# ADF_2nd_LO_board.net
KiCad netlist of a schematic drawn in Altium Designer
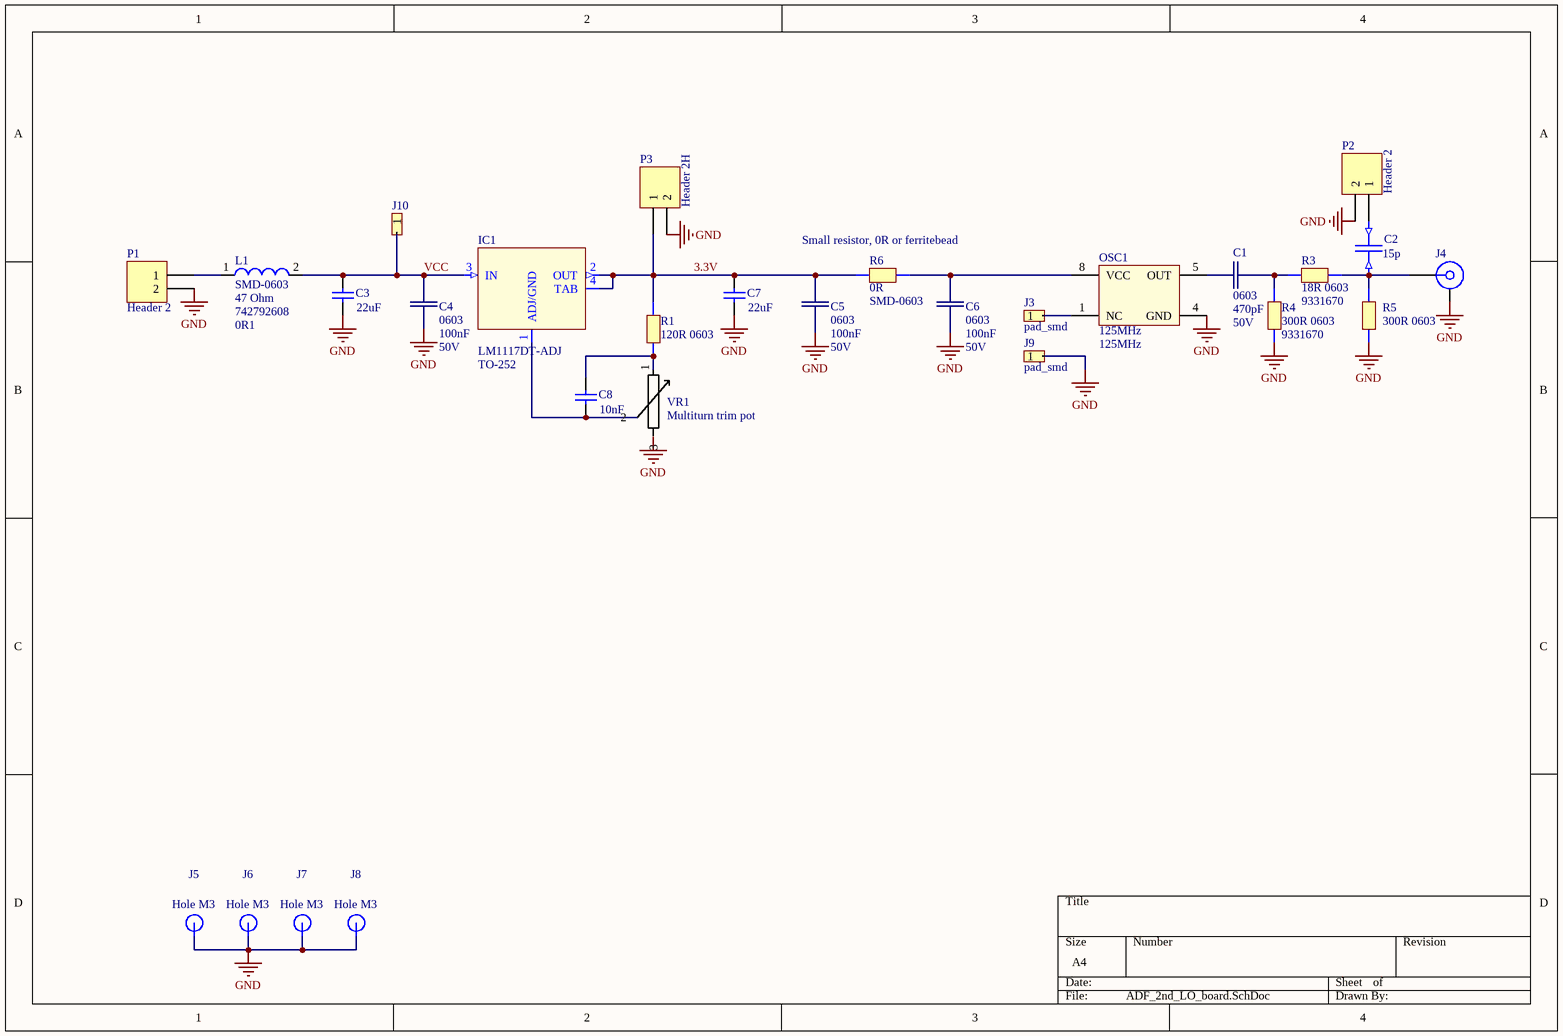
[diagram p0: ADF_2nd_LO_board.SchDoc]

(export (version "E")
  (design (tool "Eeschema 10.0.6"))
  (components
    (comp (ref "C1")
      (value "10nF 0603 NP0")
      (footprint "C0603_murata")
      (description "10nF 0603 NP0 muRata")
      (fields
        (field (name "TOLERANCE") "5%")
        (field (name "CASE CODE (IMPERIAL)") "0603")
        (field (name "CAPACITANCE") "470pF")
        (field (name "VOLTAGE") "50V")
      )
      (libsource (lib "ftg_lib") (part "10nF 0603 NP0"))
    )
    (comp (ref "C2")
      (value "15p")
      (footprint "CAPC1005X04N_0402")
      (description "Class 1 SMD Capacitor")
      (fields
        (field (name "MANUFACTURER") "AVX")
        (field (name "TOLERANCE") "± 5%")
        (field (name "PUBLISHER") "atr")
      )
      (libsource (lib "AQA_atr_2013") (part "Capacitor_15p_0402_C0G"))
    )
    (comp (ref "C3")
      (value "22uF")
      (footprint "C1206")
      (description "Capacitor (Semiconductor SIM Model)")
      (fields (field (name "Comment") "Cap Semi") (field (name "PUBLISHER") "Altium Limited"))
      (libsource (lib "Miscellaneous Devices") (part "Cap Semi"))
    )
    (comp (ref "C4")
      (value "10nF 0603 NP0")
      (footprint "C0603_murata")
      (description "10nF 0603 NP0 muRata")
      (fields
        (field (name "TOLERANCE") "5%")
        (field (name "CASE CODE (IMPERIAL)") "0603")
        (field (name "CAPACITANCE") "100nF")
        (field (name "VOLTAGE") "50V")
      )
      (libsource (lib "ftg_lib") (part "10nF 0603 NP0"))
    )
    (comp (ref "C5")
      (value "10nF 0603 NP0")
      (footprint "C0603_murata")
      (description "10nF 0603 NP0 muRata")
      (fields
        (field (name "TOLERANCE") "5%")
        (field (name "CASE CODE (IMPERIAL)") "0603")
        (field (name "CAPACITANCE") "100nF")
        (field (name "VOLTAGE") "50V")
      )
      (libsource (lib "ftg_lib") (part "10nF 0603 NP0"))
    )
    (comp (ref "C6")
      (value "10nF 0603 NP0")
      (footprint "C0603_murata")
      (description "10nF 0603 NP0 muRata")
      (fields
        (field (name "TOLERANCE") "5%")
        (field (name "CASE CODE (IMPERIAL)") "0603")
        (field (name "CAPACITANCE") "100nF")
        (field (name "VOLTAGE") "50V")
      )
      (libsource (lib "ftg_lib") (part "10nF 0603 NP0"))
    )
    (comp (ref "C7")
      (value "22uF")
      (footprint "C1206")
      (description "Capacitor (Semiconductor SIM Model)")
      (fields (field (name "Comment") "Cap Semi") (field (name "PUBLISHER") "Altium Limited"))
      (libsource (lib "Miscellaneous Devices") (part "Cap Semi"))
    )
    (comp (ref "C8")
      (value "10nF")
      (footprint "1608[0603]")
      (description "Capacitor (Semiconductor SIM Model)")
      (fields (field (name "Comment") "Cap Semi") (field (name "PUBLISHER") "Altium Limited"))
      (libsource (lib "Miscellaneous Devices") (part "Cap Semi"))
    )
    (comp (ref "IC1")
      (value "LM1117DT-ADJ")
      (footprint "TO-252")
      (description "TEXAS INSTRUMENTS  LM1117DT-ADJ  V REG ADJ +1.25/13.8V, 1117, DPAK-3")
      (fields
        (field (name "MANUFACTURER") "TEXAS INSTRUMENTS")
        (field (name "VOLTAGE") "1.25V - 13.8V")
        (field (name "PACKAGEREFERENCE") "TO-252")
        (field (name "PUBLISHER") "atr")
      )
      (libsource (lib "AQA_atr_2013") (part "LM1117DT-ADJ"))
    )
    (comp (ref "J3")
      (value "pad_smd")
      (footprint "pad_smd_bodge")
      (description "1mm * 2mm smd pad")
      (libsource (lib "AQA_Ismolib") (part "pad_smd_1mm*2mm"))
    )
    (comp (ref "J4")
      (value "32K201-400L5")
      (footprint "ROS-32K201-400L5_V")
      (description "SMA Right Angle Jack, Up to 18 GHz, -65 to 165 degC")
      (libsource (lib "Rosenberger SMA") (part "32K201-400L5"))
    )
    (comp (ref "J5")
      (value "Hole M3")
      (footprint "HOLE_M3")
      (description "HoleM3")
      (fields (field (name "TOLERANCE") "N.A.") (field (name "PUBLISHER") "atr"))
      (libsource (lib "AQA_atr_2013") (part "HoleM3"))
    )
    (comp (ref "J6")
      (value "Hole M3")
      (footprint "HOLE_M3")
      (description "HoleM3")
      (fields (field (name "TOLERANCE") "N.A.") (field (name "PUBLISHER") "atr"))
      (libsource (lib "AQA_atr_2013") (part "HoleM3"))
    )
    (comp (ref "J7")
      (value "Hole M3")
      (footprint "HOLE_M3")
      (description "HoleM3")
      (fields (field (name "TOLERANCE") "N.A.") (field (name "PUBLISHER") "atr"))
      (libsource (lib "AQA_atr_2013") (part "HoleM3"))
    )
    (comp (ref "J8")
      (value "Hole M3")
      (footprint "HOLE_M3")
      (description "HoleM3")
      (fields (field (name "TOLERANCE") "N.A.") (field (name "PUBLISHER") "atr"))
      (libsource (lib "AQA_atr_2013") (part "HoleM3"))
    )
    (comp (ref "J9")
      (value "pad_smd")
      (footprint "pad_smd_bodge")
      (description "1mm * 2mm smd pad")
      (libsource (lib "AQA_Ismolib") (part "pad_smd_1mm*2mm"))
    )
    (comp (ref "J10")
      (value "pad_smd")
      (footprint "pad_smd_bodge")
      (description "1mm * 2mm smd pad")
      (libsource (lib "") (part "pad_smd_1mm*2mm_1"))
    )
    (comp (ref "L1")
      (value "742792608")
      (footprint "SMD-0603")
      (description "SMD EMI Suppression Ferrite Bead WE-CBF, Z = 47 Ohm")
      (fields
        (field (name "PACKAGEREFERENCE") "SMD-0603")
        (field (name "IMPEDANCE") "47 Ohm")
        (field (name "DC_RESISTANCE") "0R1")
      )
      (libsource (lib "AQA_20007_4_Flange") (part "742792608"))
    )
    (comp (ref "OSC1")
      (value "125MHz")
      (footprint "DIP-8_osc")
      (description "DIP Oscillator")
      (fields (field (name "FREQUENCY") "125MHz") (field (name "PUBLISHER") "ftg"))
      (libsource (lib "ftg_lib") (part "OSC DIP-8 125MHz 3.3V TTL"))
    )
    (comp (ref "P1")
      (value "Header 2")
      (footprint "HDR1X2")
      (description "Header, 2-Pin")
      (fields (field (name "PUBLISHER") "Altium Limited"))
      (libsource (lib "Miscellaneous Connectors") (part "Header 2"))
    )
    (comp (ref "P2")
      (value "Header 2")
      (footprint "HDR1X2")
      (description "Header, 2-Pin")
      (fields (field (name "PUBLISHER") "Altium Limited"))
      (libsource (lib "") (part "Header 2_1"))
    )
    (comp (ref "P3")
      (value "Header 2H")
      (footprint "HDR1X2H")
      (description "Header, 2-Pin, Right Angle")
      (fields (field (name "PUBLISHER") "Altium Limited"))
      (libsource (lib "Miscellaneous Connectors") (part "Header 2H"))
    )
    (comp (ref "R1")
      (value "120R 0603")
      (footprint "R0603")
      (fields (field (name "MANUFACTURER") "YAGEO (PHYCOMP)") (field (name "PUBLISHER") "iv"))
      (libsource (lib "AQA_Ismolib") (part "0603 120R"))
    )
    (comp (ref "R3")
      (value "18R 0603")
      (footprint "R0603")
      (description "10R 0603")
      (fields
        (field (name "MANUFACTURER") "MULTICOMP")
        (field (name "ORDERCODE") "9331670")
        (field (name "PUBLISHER") "iv")
      )
      (libsource (lib "AQA_Ismolib") (part "0603 10R"))
    )
    (comp (ref "R4")
      (value "300R 0603")
      (footprint "R0603")
      (description "10R 0603")
      (fields
        (field (name "MANUFACTURER") "MULTICOMP")
        (field (name "ORDERCODE") "9331670")
        (field (name "PUBLISHER") "iv")
      )
      (libsource (lib "") (part "0603 10R_2"))
    )
    (comp (ref "R5")
      (value "300R 0603")
      (footprint "R0603")
      (description "10R 0603")
      (fields (field (name "MANUFACTURER") "MULTICOMP") (field (name "PUBLISHER") "iv"))
      (libsource (lib "") (part "0603 10R_1"))
    )
    (comp (ref "R6")
      (value "0R")
      (footprint "RESC1608X06N_0603")
      (description "Bulk SMD Resistor")
      (fields
        (field (name "MANUFACTURER") "PANASONIC")
        (field (name "VOLTAGE") "75V")
        (field (name "PACKAGEREFERENCE") "SMD-0603")
        (field (name "PUBLISHER") "atr")
      )
      (libsource (lib "AQA_atr_2013") (part "Resistor_0R_0603_Bulk"))
    )
    (comp (ref "VR1")
      (value "Multiturn trim pot")
      (footprint "Multiturn trimpot flat long")
      (libsource (lib "AQA_Ismolib") (part "Multiturn trim pot"))
    )
  )
  (nets
    (net (code "1") (name "/3.3V") (class "Default")
      (node (ref "C5") (pin "1") (pinfunction "1_1") (pintype "passive"))
      (node (ref "C7") (pin "2") (pinfunction "2_2") (pintype "passive"))
      (node (ref "IC1") (pin "2") (pinfunction "OUT_2") (pintype "output"))
      (node (ref "IC1") (pin "4") (pinfunction "TAB_4") (pintype "passive"))
      (node (ref "P3") (pin "1") (pinfunction "1_1") (pintype "passive"))
      (node (ref "R1") (pin "1") (pinfunction "1_1") (pintype "passive"))
      (node (ref "R6") (pin "1") (pinfunction "1_1") (pintype "passive"))
    )
    (net (code "2") (name "/VCC") (class "Default")
      (node (ref "C3") (pin "2") (pinfunction "2_2") (pintype "passive"))
      (node (ref "C4") (pin "1") (pinfunction "1_1") (pintype "passive"))
      (node (ref "IC1") (pin "3") (pinfunction "IN_3") (pintype "input"))
      (node (ref "J10") (pin "1") (pinfunction "1_1") (pintype "passive"))
      (node (ref "L1") (pin "2") (pinfunction "2_2") (pintype "passive"))
    )
    (net (code "3") (name "GND") (class "Default")
      (node (ref "C3") (pin "1") (pinfunction "1_1") (pintype "passive"))
      (node (ref "C5") (pin "2") (pinfunction "2_2") (pintype "passive"))
      (node (ref "C6") (pin "2") (pinfunction "2_2") (pintype "passive"))
      (node (ref "C7") (pin "1") (pinfunction "1_1") (pintype "passive"))
      (node (ref "J4") (pin "MH") (pinfunction "MH_MH") (pintype "passive"))
      (node (ref "J5") (pin "1") (pinfunction "1_1") (pintype "bidirectional"))
      (node (ref "J6") (pin "1") (pinfunction "1_1") (pintype "bidirectional"))
      (node (ref "J7") (pin "1") (pinfunction "1_1") (pintype "bidirectional"))
      (node (ref "J8") (pin "1") (pinfunction "1_1") (pintype "bidirectional"))
      (node (ref "J9") (pin "1") (pinfunction "1_1") (pintype "passive"))
      (node (ref "OSC1") (pin "4") (pinfunction "GND_4") (pintype "passive"))
      (node (ref "P1") (pin "2") (pinfunction "2_2") (pintype "passive"))
      (node (ref "P2") (pin "2") (pinfunction "2_2") (pintype "passive"))
      (node (ref "P3") (pin "2") (pinfunction "2_2") (pintype "passive"))
      (node (ref "R4") (pin "2") (pinfunction "2_2") (pintype "passive"))
      (node (ref "R5") (pin "1") (pinfunction "1_1") (pintype "passive"))
    )
    (net (code "4") (name "Net-(C1-Pad2)") (class "Default")
      (node (ref "C1") (pin "2") (pinfunction "2_2") (pintype "passive"))
      (node (ref "R3") (pin "2") (pinfunction "2_2") (pintype "passive"))
      (node (ref "R4") (pin "1") (pinfunction "1_1") (pintype "passive"))
    )
    (net (code "5") (name "Net-(C2-Pad1)") (class "Default")
      (node (ref "C2") (pin "1") (pinfunction "1_1") (pintype "input"))
      (node (ref "J4") (pin "1") (pinfunction "1_1") (pintype "passive"))
      (node (ref "R3") (pin "1") (pinfunction "1_1") (pintype "passive"))
      (node (ref "R5") (pin "2") (pinfunction "2_2") (pintype "passive"))
    )
    (net (code "6") (name "Net-(C2-Pad2)") (class "Default")
      (node (ref "C2") (pin "2") (pinfunction "2_2") (pintype "input"))
      (node (ref "P2") (pin "1") (pinfunction "1_1") (pintype "passive"))
    )
    (net (code "7") (name "Net-(C8-Pad2)") (class "Default")
      (node (ref "C8") (pin "2") (pinfunction "2_2") (pintype "passive"))
      (node (ref "R1") (pin "2") (pinfunction "2_2") (pintype "passive"))
      (node (ref "VR1") (pin "1") (pinfunction "1_1") (pintype "passive"))
    )
    (net (code "8") (name "Net-(IC1-ADJ{slash}GND)") (class "Default")
      (node (ref "C8") (pin "1") (pinfunction "1_1") (pintype "passive"))
      (node (ref "IC1") (pin "1") (pinfunction "ADJ/GND_1") (pintype "passive"))
      (node (ref "VR1") (pin "2") (pinfunction "2_2") (pintype "passive"))
    )
    (net (code "9") (name "Net-(L1-Pad1)") (class "Default")
      (node (ref "L1") (pin "1") (pinfunction "1_1") (pintype "passive"))
      (node (ref "P1") (pin "1") (pinfunction "1_1") (pintype "passive"))
    )
    (net (code "10") (name "Net-(OSC1-NC)") (class "Default")
      (node (ref "J3") (pin "1") (pinfunction "1_1") (pintype "passive"))
      (node (ref "OSC1") (pin "1") (pinfunction "NC_1") (pintype "passive"))
    )
    (net (code "11") (name "Net-(OSC1-OUT)") (class "Default")
      (node (ref "C1") (pin "1") (pinfunction "1_1") (pintype "passive"))
      (node (ref "OSC1") (pin "5") (pinfunction "OUT_5") (pintype "passive"))
    )
    (net (code "12") (name "Net-(OSC1-VCC)") (class "Default")
      (node (ref "C6") (pin "1") (pinfunction "1_1") (pintype "passive"))
      (node (ref "OSC1") (pin "8") (pinfunction "VCC_8") (pintype "passive"))
      (node (ref "R6") (pin "2") (pinfunction "2_2") (pintype "passive"))
    )
    (net (code "13") (name "unconnected-(C4-Pad2)") (class "Default")
      (node (ref "C4") (pin "2") (pinfunction "2_2") (pintype "passive"))
    )
    (net (code "14") (name "unconnected-(VR1-Pad3)") (class "Default")
      (node (ref "VR1") (pin "3") (pinfunction "3_3") (pintype "passive"))
    )
  )
)
